# Regulated_4A_Adjustable_Circuit.net
KiCad netlist of a schematic drawn in EAGLE
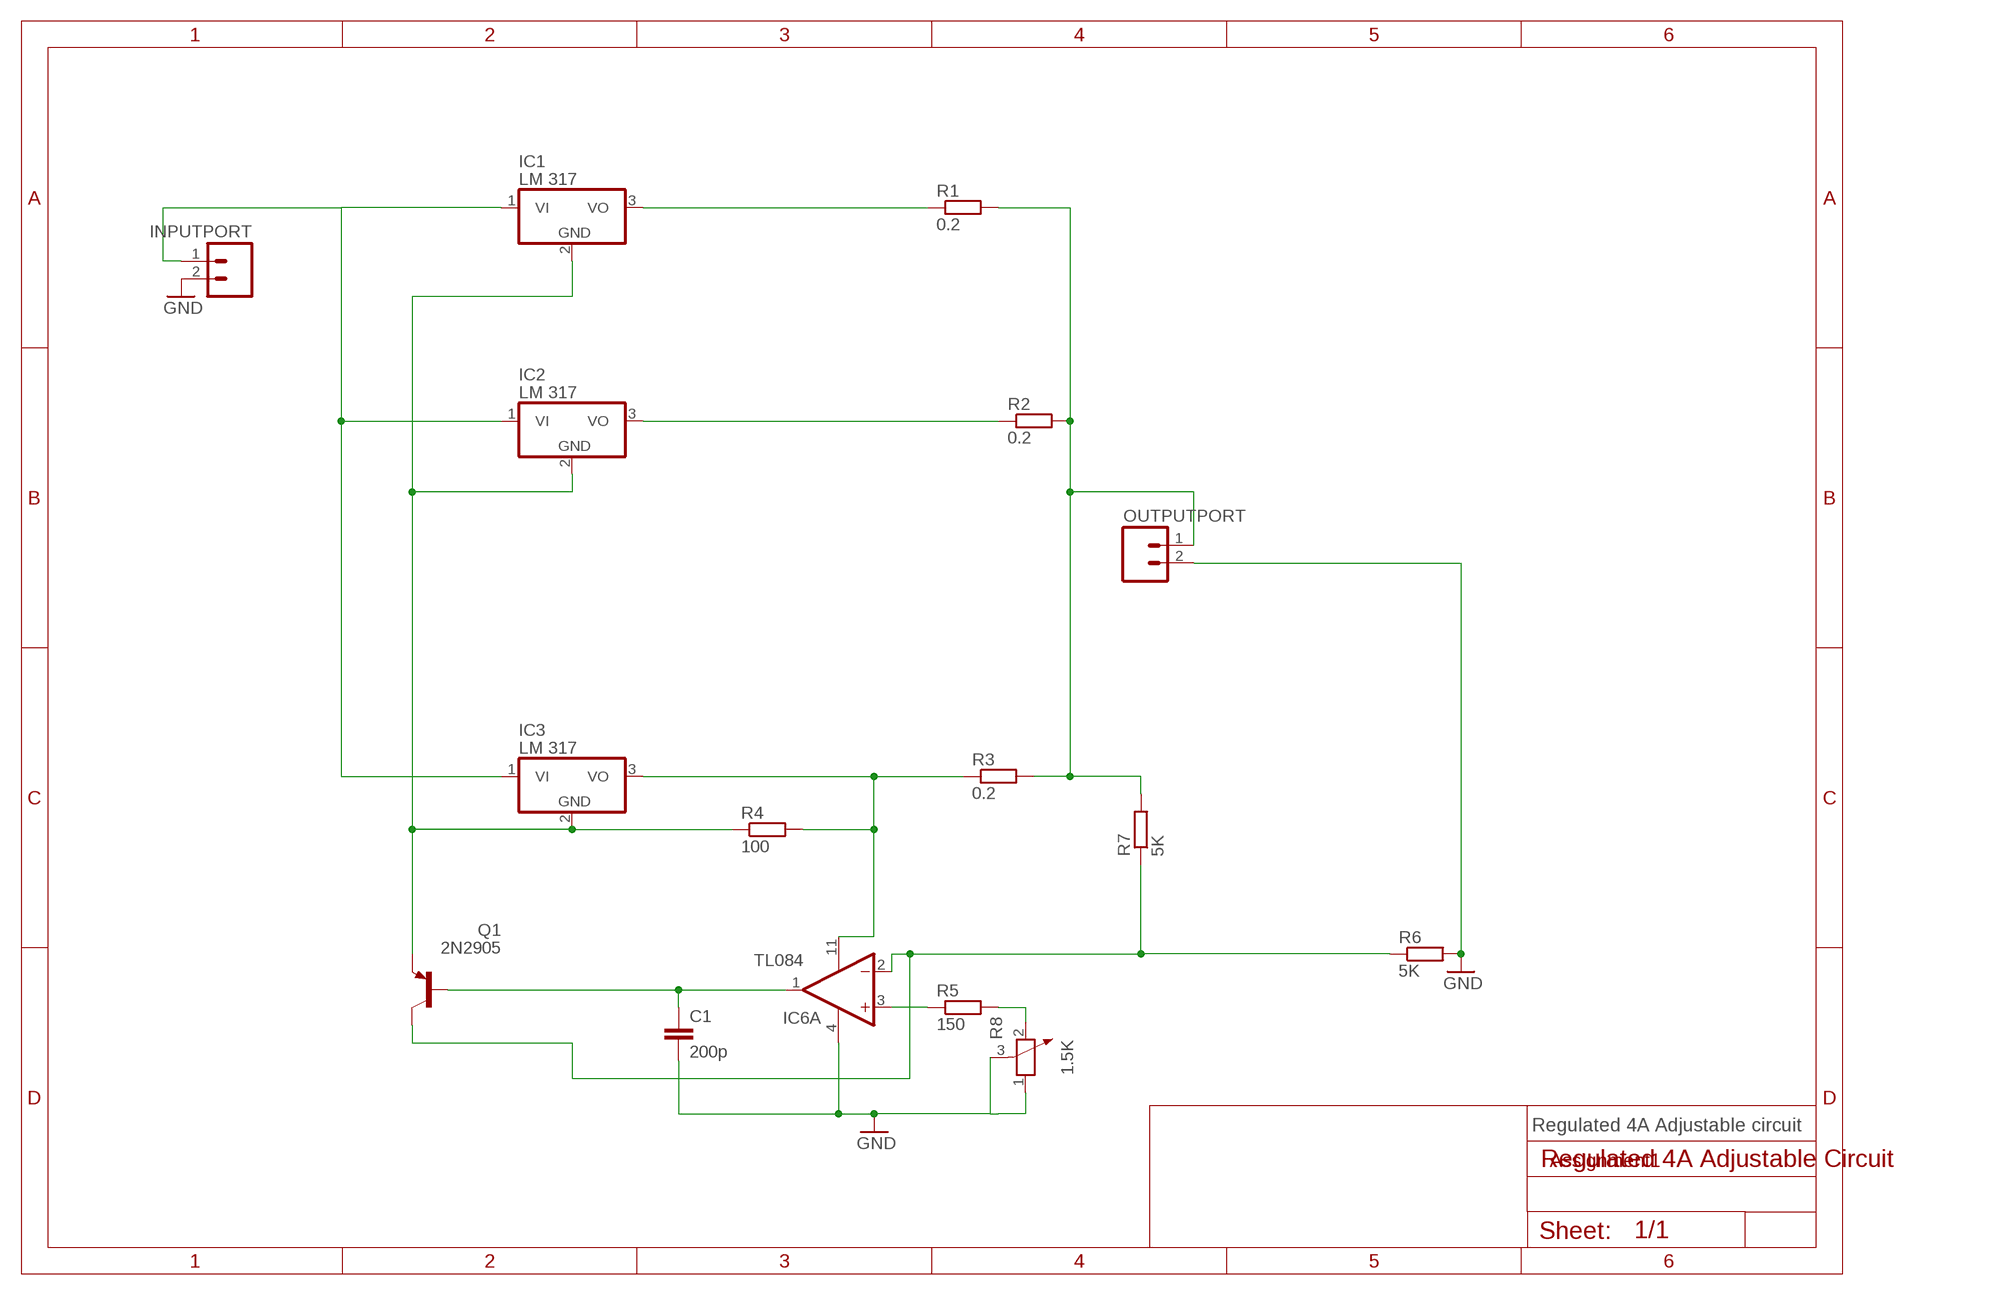
[diagram p0: schematic, sheet 1]

(export (version "E")
  (design (tool "Eeschema 10.0.6"))
  (components
    (comp (ref "C1")
      (value "200p")
      (footprint "eagle-import:C025-025X050")
      (libsource (lib "eagle-import") (part "C-EU025-025X050"))
    )
    (comp (ref "IC1")
      (value "LM 317")
      (footprint "eagle-import:TO220V")
      (libsource (lib "eagle-import") (part "78TV05"))
    )
    (comp (ref "IC2")
      (value "LM 317")
      (footprint "eagle-import:TO220V")
      (libsource (lib "eagle-import") (part "78TV05"))
    )
    (comp (ref "IC3")
      (value "LM 317")
      (footprint "eagle-import:TO220V")
      (libsource (lib "eagle-import") (part "78TV05"))
    )
    (comp (ref "IC6")
      (value "TL084")
      (footprint "eagle-import:DIL14")
      (libsource (lib "eagle-import") (part "MCP604P"))
    )
    (comp (ref "Q1")
      (value "2N2905")
      (footprint "eagle-import:TO39")
      (libsource (lib "eagle-import") (part "2N2905"))
    )
    (comp (ref "R1")
      (value "0.2")
      (footprint "eagle-import:0207_10")
      (libsource (lib "eagle-import") (part "R-EU_0207/10"))
    )
    (comp (ref "R2")
      (value "0.2")
      (footprint "eagle-import:0207_10")
      (libsource (lib "eagle-import") (part "R-EU_0207/10"))
    )
    (comp (ref "R3")
      (value "0.2")
      (footprint "eagle-import:0207_10")
      (libsource (lib "eagle-import") (part "R-EU_0207/10"))
    )
    (comp (ref "R4")
      (value "100")
      (footprint "eagle-import:0207_10")
      (libsource (lib "eagle-import") (part "R-EU_0207/10"))
    )
    (comp (ref "R5")
      (value "150")
      (footprint "eagle-import:0207_10")
      (libsource (lib "eagle-import") (part "R-EU_0207/10"))
    )
    (comp (ref "R6")
      (value "5K")
      (footprint "eagle-import:0207_10")
      (libsource (lib "eagle-import") (part "R-EU_0207/10"))
    )
    (comp (ref "R7")
      (value "5K")
      (footprint "eagle-import:0207_10")
      (libsource (lib "eagle-import") (part "R-EU_0207/10"))
    )
    (comp (ref "R8")
      (value "1.5K")
      (footprint "eagle-import:PT-10")
      (libsource (lib "eagle-import") (part "POTENTIOMETER_PT-10"))
    )
    (comp (ref "SL1")
      (value "INPUTPORT")
      (footprint "eagle-import:02P")
      (libsource (lib "eagle-import") (part "M02"))
    )
    (comp (ref "SL2")
      (value "OUTPUTPORT")
      (footprint "eagle-import:02P")
      (libsource (lib "eagle-import") (part "M02"))
    )
  )
  (nets
    (net (code "1") (name "GND") (class "Default")
      (node (ref "C1") (pin "2") (pinfunction "2_2") (pintype "passive"))
      (node (ref "IC6") (pin "4") (pinfunction "V+_4") (pintype "power_in"))
      (node (ref "R6") (pin "2") (pinfunction "2_2") (pintype "passive"))
      (node (ref "R8") (pin "1") (pinfunction "1_1") (pintype "passive"))
      (node (ref "R8") (pin "3") (pinfunction "3_3") (pintype "passive"))
      (node (ref "SL1") (pin "2") (pinfunction "2_2") (pintype "passive"))
      (node (ref "SL2") (pin "2") (pinfunction "2_2") (pintype "passive"))
    )
    (net (code "2") (name "Net-(IC1-GND)") (class "Default")
      (node (ref "IC1") (pin "2") (pinfunction "GND_2") (pintype "passive"))
      (node (ref "IC2") (pin "2") (pinfunction "GND_2") (pintype "passive"))
      (node (ref "IC3") (pin "2") (pinfunction "GND_2") (pintype "passive"))
      (node (ref "Q1") (pin "1") (pinfunction "E_1") (pintype "passive"))
      (node (ref "R4") (pin "1") (pinfunction "1_1") (pintype "passive"))
    )
    (net (code "3") (name "Net-(IC1-VI)") (class "Default")
      (node (ref "IC1") (pin "1") (pinfunction "VI_1") (pintype "input"))
      (node (ref "IC2") (pin "1") (pinfunction "VI_1") (pintype "input"))
      (node (ref "IC3") (pin "1") (pinfunction "VI_1") (pintype "input"))
      (node (ref "SL1") (pin "1") (pinfunction "1_1") (pintype "passive"))
    )
    (net (code "4") (name "Net-(IC1-VO)") (class "Default")
      (node (ref "IC1") (pin "3") (pinfunction "VO_3") (pintype "passive"))
      (node (ref "R1") (pin "1") (pinfunction "1_1") (pintype "passive"))
    )
    (net (code "5") (name "Net-(IC2-VO)") (class "Default")
      (node (ref "IC2") (pin "3") (pinfunction "VO_3") (pintype "passive"))
      (node (ref "R2") (pin "1") (pinfunction "1_1") (pintype "passive"))
    )
    (net (code "6") (name "Net-(IC3-VO)") (class "Default")
      (node (ref "IC3") (pin "3") (pinfunction "VO_3") (pintype "passive"))
      (node (ref "IC6") (pin "11") (pinfunction "V-_11") (pintype "power_in"))
      (node (ref "R3") (pin "1") (pinfunction "1_1") (pintype "passive"))
      (node (ref "R4") (pin "2") (pinfunction "2_2") (pintype "passive"))
    )
    (net (code "7") (name "Net-(IC6A-+IN)") (class "Default")
      (node (ref "IC6") (pin "3") (pinfunction "+IN_3") (pintype "input"))
      (node (ref "R5") (pin "1") (pinfunction "1_1") (pintype "passive"))
    )
    (net (code "8") (name "Net-(IC6A--IN)") (class "Default")
      (node (ref "IC6") (pin "2") (pinfunction "-IN_2") (pintype "input"))
      (node (ref "Q1") (pin "3") (pinfunction "C_3") (pintype "passive"))
      (node (ref "R6") (pin "1") (pinfunction "1_1") (pintype "passive"))
      (node (ref "R7") (pin "1") (pinfunction "1_1") (pintype "passive"))
    )
    (net (code "9") (name "Net-(IC6A-OUT)") (class "Default")
      (node (ref "C1") (pin "1") (pinfunction "1_1") (pintype "passive"))
      (node (ref "IC6") (pin "1") (pinfunction "OUT_1") (pintype "output"))
      (node (ref "Q1") (pin "2") (pinfunction "B_2") (pintype "passive"))
    )
    (net (code "10") (name "Net-(R1-Pad2)") (class "Default")
      (node (ref "R1") (pin "2") (pinfunction "2_2") (pintype "passive"))
      (node (ref "R2") (pin "2") (pinfunction "2_2") (pintype "passive"))
      (node (ref "R3") (pin "2") (pinfunction "2_2") (pintype "passive"))
      (node (ref "R7") (pin "2") (pinfunction "2_2") (pintype "passive"))
      (node (ref "SL2") (pin "1") (pinfunction "1_1") (pintype "passive"))
    )
    (net (code "11") (name "Net-(R5-Pad2)") (class "Default")
      (node (ref "R5") (pin "2") (pinfunction "2_2") (pintype "passive"))
      (node (ref "R8") (pin "2") (pinfunction "2_2") (pintype "passive"))
    )
  )
)
